# mix_txmix.net
KiCad netlist of a schematic drawn in Altium Designer
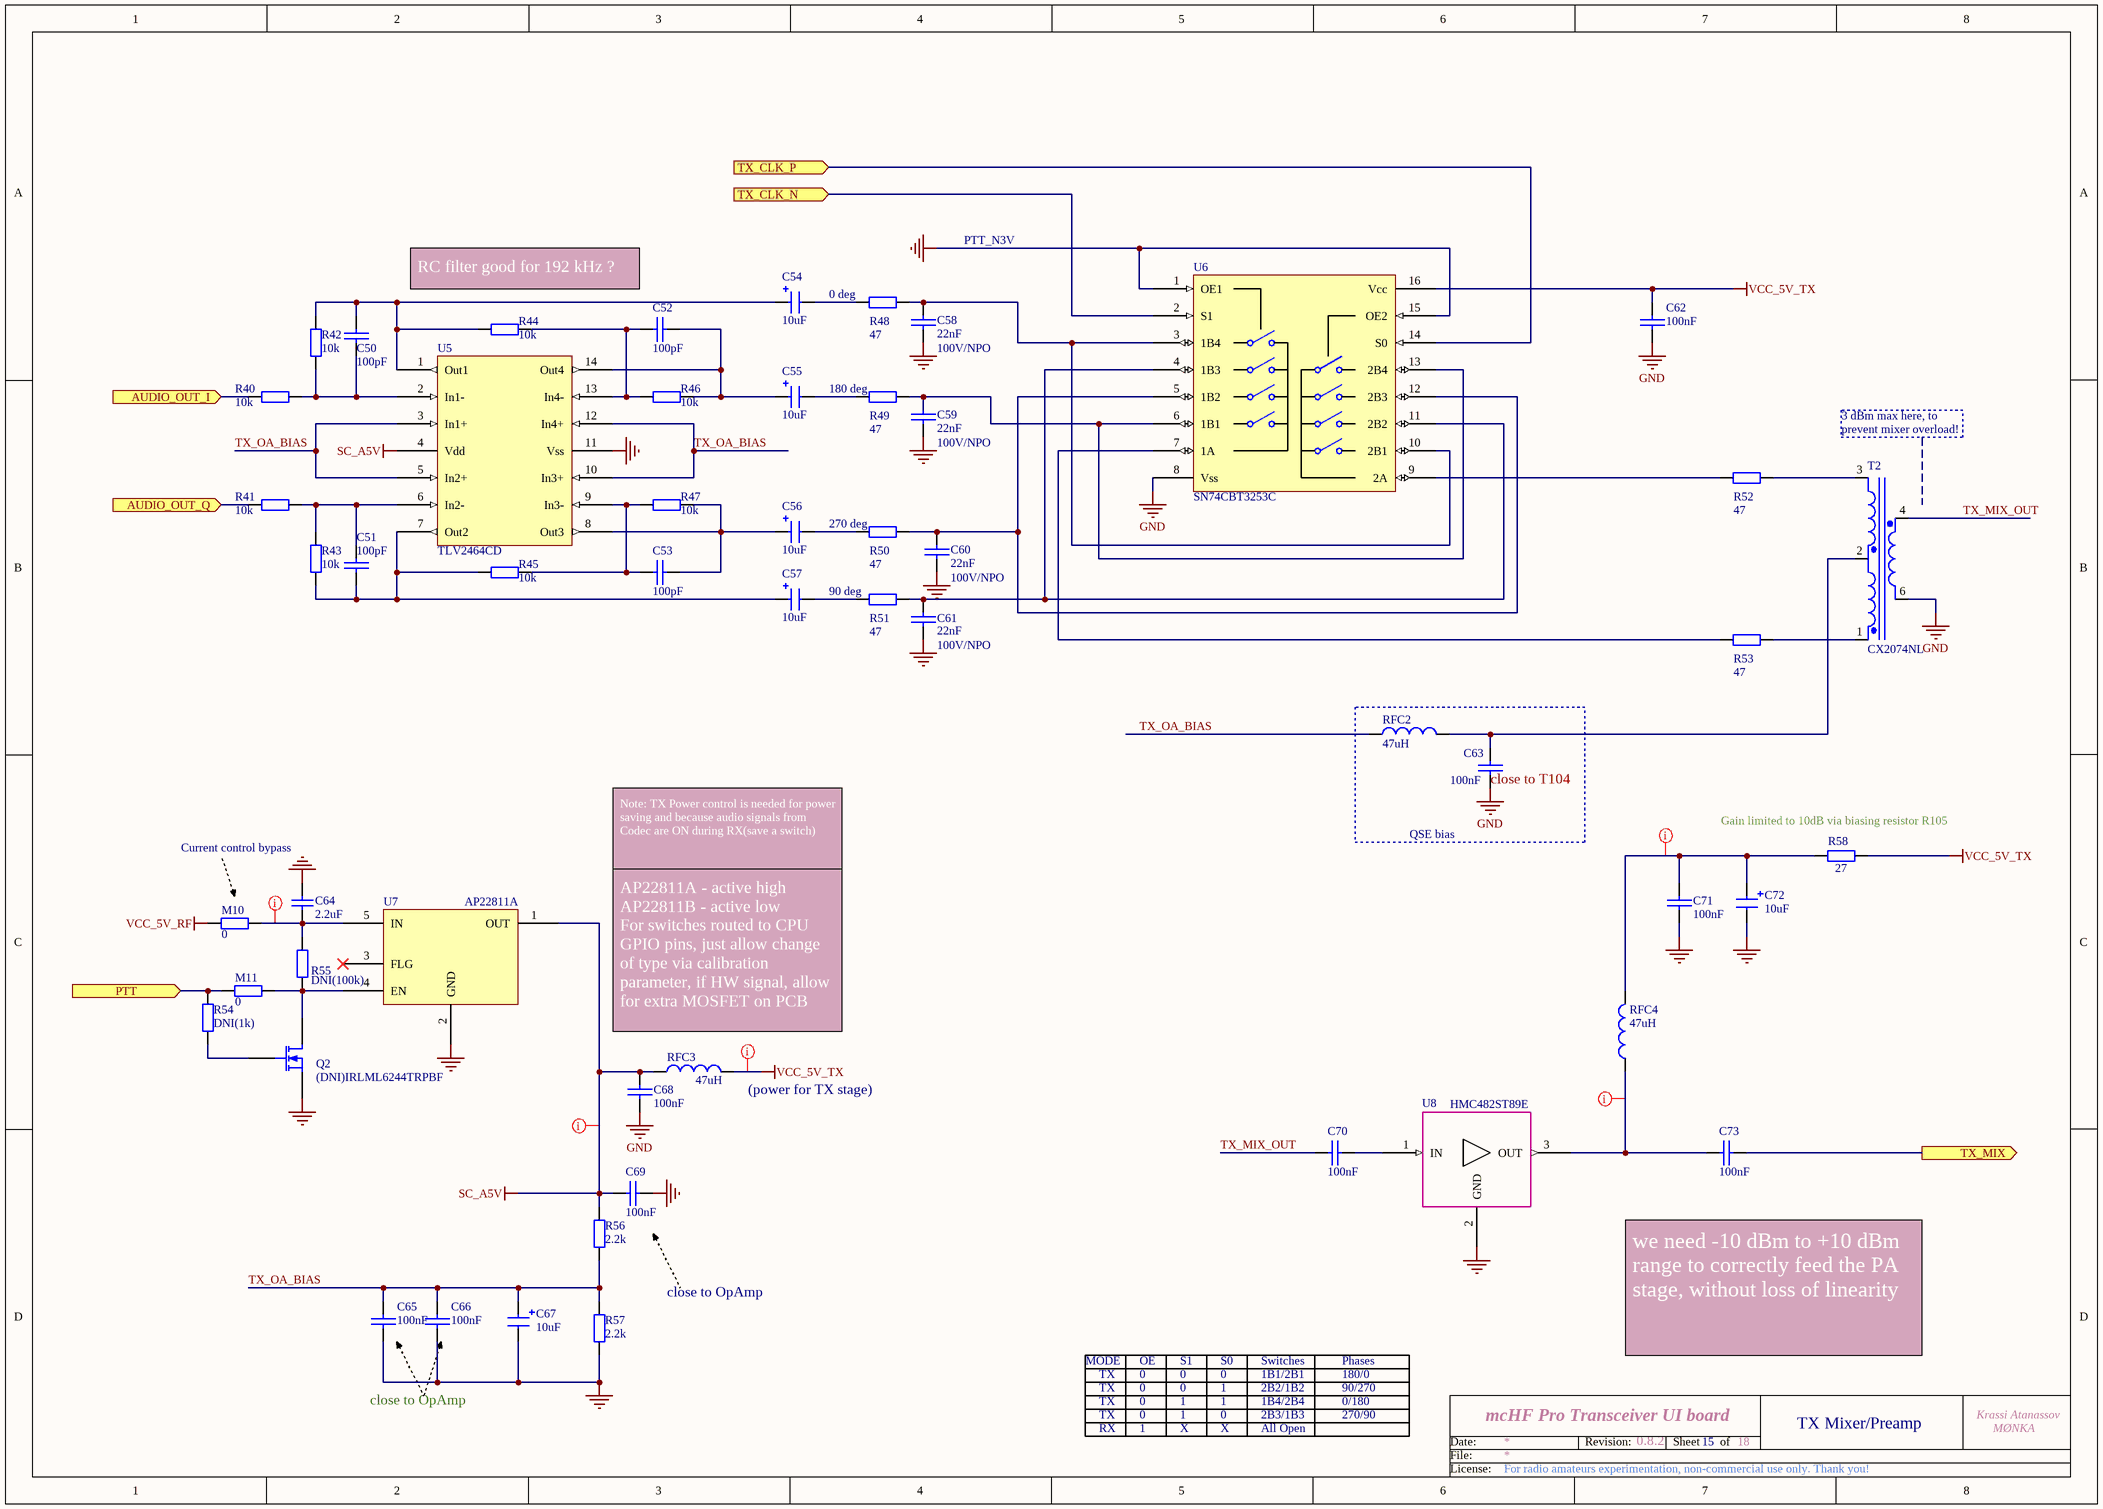
[diagram p0: mix_txmix.SchDoc]

(export (version "E")
  (design (tool "Eeschema 10.0.6"))
  (components
    (comp (ref "C50")
      (value "100pF")
      (footprint "0805")
      (description "Capacitor")
      (libsource (lib "mcHF_rf") (part "CAP"))
    )
    (comp (ref "C51")
      (value "100pF")
      (footprint "0805")
      (description "Capacitor")
      (libsource (lib "mcHF_rf") (part "CAP"))
    )
    (comp (ref "C52")
      (value "100pF")
      (footprint "0805")
      (description "Capacitor")
      (libsource (lib "mcHF_rf") (part "CAP"))
    )
    (comp (ref "C53")
      (value "100pF")
      (footprint "0805")
      (description "Capacitor")
      (libsource (lib "mcHF_rf") (part "CAP"))
    )
    (comp (ref "C54")
      (value "10uF")
      (footprint "1206_Elec_Cap")
      (description "Electrolitic capacitor")
      (libsource (lib "mcHF_rf") (part "CAP-POL"))
    )
    (comp (ref "C55")
      (value "10uF")
      (footprint "1206_Elec_Cap")
      (description "Electrolitic capacitor")
      (libsource (lib "mcHF_rf") (part "CAP-POL"))
    )
    (comp (ref "C56")
      (value "10uF")
      (footprint "1206_Elec_Cap")
      (description "Electrolitic capacitor")
      (libsource (lib "mcHF_rf") (part "CAP-POL"))
    )
    (comp (ref "C57")
      (value "10uF")
      (footprint "1206_Elec_Cap")
      (description "Electrolitic capacitor")
      (libsource (lib "mcHF_rf") (part "CAP-POL"))
    )
    (comp (ref "C58")
      (value "22nF")
      (footprint "CAP_B")
      (description "Capacitor")
      (fields (field (name "VOLTAGE") "100V/NPO"))
      (libsource (lib "mcHF_rf") (part "CAP"))
    )
    (comp (ref "C59")
      (value "22nF")
      (footprint "CAP_B")
      (description "Capacitor")
      (fields (field (name "VOLTAGE") "100V/NPO"))
      (libsource (lib "mcHF_rf") (part "CAP"))
    )
    (comp (ref "C60")
      (value "22nF")
      (footprint "CAP_B")
      (description "Capacitor")
      (fields (field (name "VOLTAGE") "100V/NPO"))
      (libsource (lib "mcHF_rf") (part "CAP"))
    )
    (comp (ref "C61")
      (value "22nF")
      (footprint "CAP_B")
      (description "Capacitor")
      (fields (field (name "VOLTAGE") "100V/NPO"))
      (libsource (lib "mcHF_rf") (part "CAP"))
    )
    (comp (ref "C62")
      (value "100nF")
      (footprint "0805")
      (description "Capacitor")
      (libsource (lib "mcHF_rf") (part "CAP"))
    )
    (comp (ref "C63")
      (value "100nF")
      (footprint "0805")
      (description "Capacitor")
      (libsource (lib "mcHF_rf") (part "CAP"))
    )
    (comp (ref "C64")
      (value "2.2uF")
      (footprint "0805")
      (description "0603  X5R 1礔")
      (fields (field (name "TOLERANCE") "10%"))
      (libsource (lib "MB963_1") (part "CAP SMD 0603  X5R 1礔 25V 10%"))
    )
    (comp (ref "C65")
      (value "100nF")
      (footprint "0805")
      (description "Capacitor")
      (libsource (lib "mcHF_rf") (part "CAP"))
    )
    (comp (ref "C66")
      (value "100nF")
      (footprint "0805")
      (description "Capacitor")
      (libsource (lib "mcHF_rf") (part "CAP"))
    )
    (comp (ref "C67")
      (value "10uF")
      (footprint "1206_Elec_Cap")
      (description "Electrolitic capacitor")
      (libsource (lib "mcHF_rf") (part "CAP-POL"))
    )
    (comp (ref "C68")
      (value "100nF")
      (footprint "0805")
      (description "Capacitor")
      (libsource (lib "mcHF_rf") (part "CAP"))
    )
    (comp (ref "C69")
      (value "100nF")
      (footprint "0805")
      (description "Capacitor")
      (libsource (lib "mcHF_rf") (part "CAP"))
    )
    (comp (ref "C70")
      (value "100nF")
      (footprint "0805")
      (description "Capacitor")
      (libsource (lib "*") (part "CAP"))
    )
    (comp (ref "C71")
      (value "100nF")
      (footprint "0805")
      (description "Capacitor")
      (libsource (lib "*") (part "CAP"))
    )
    (comp (ref "C72")
      (value "10uF")
      (footprint "1206_Elec_Cap")
      (description "Electrolitic capacitor")
      (libsource (lib "mcHF_rf") (part "CAP-POL"))
    )
    (comp (ref "C73")
      (value "100nF")
      (footprint "0805")
      (description "Capacitor")
      (libsource (lib "*") (part "CAP"))
    )
    (comp (ref "M10")
      (value "0")
      (footprint "0805")
      (description "Resistor")
      (libsource (lib "mcHF_rf") (part "RES"))
    )
    (comp (ref "M11")
      (value "0")
      (footprint "0805")
      (description "Resistor")
      (libsource (lib "") (part "RES_1"))
    )
    (comp (ref "Q2")
      (value "(DNI)IRLML6244TRPBF")
      (footprint "SOT-23")
      (description "N-Channel MOSFET")
      (libsource (lib "mcHF_ui_b") (part "MOSFET-N"))
    )
    (comp (ref "R40")
      (value "10k")
      (footprint "0805")
      (description "Resistor")
      (libsource (lib "mcHF_rf") (part "RES"))
    )
    (comp (ref "R41")
      (value "10k")
      (footprint "0805")
      (description "Resistor")
      (libsource (lib "mcHF_rf") (part "RES"))
    )
    (comp (ref "R42")
      (value "10k")
      (footprint "0805")
      (description "Resistor")
      (libsource (lib "") (part "RES_2"))
    )
    (comp (ref "R43")
      (value "10k")
      (footprint "0805")
      (description "Resistor")
      (libsource (lib "") (part "RES_2"))
    )
    (comp (ref "R44")
      (value "10k")
      (footprint "0805")
      (description "Resistor")
      (libsource (lib "mcHF_rf") (part "RES"))
    )
    (comp (ref "R45")
      (value "10k")
      (footprint "0805")
      (description "Resistor")
      (libsource (lib "mcHF_rf") (part "RES"))
    )
    (comp (ref "R46")
      (value "10k")
      (footprint "0805")
      (description "Resistor")
      (libsource (lib "mcHF_rf") (part "RES"))
    )
    (comp (ref "R47")
      (value "10k")
      (footprint "0805")
      (description "Resistor")
      (libsource (lib "mcHF_rf") (part "RES"))
    )
    (comp (ref "R48")
      (value "47")
      (footprint "0805")
      (description "Resistor")
      (libsource (lib "mcHF_rf") (part "RES"))
    )
    (comp (ref "R49")
      (value "47")
      (footprint "0805")
      (description "Resistor")
      (libsource (lib "mcHF_rf") (part "RES"))
    )
    (comp (ref "R50")
      (value "47")
      (footprint "0805")
      (description "Resistor")
      (libsource (lib "mcHF_rf") (part "RES"))
    )
    (comp (ref "R51")
      (value "47")
      (footprint "0805")
      (description "Resistor")
      (libsource (lib "mcHF_rf") (part "RES"))
    )
    (comp (ref "R52")
      (value "47")
      (footprint "0805")
      (description "Resistor")
      (libsource (lib "mcHF_rf") (part "RES"))
    )
    (comp (ref "R53")
      (value "47")
      (footprint "0805")
      (description "Resistor")
      (libsource (lib "mcHF_rf") (part "RES"))
    )
    (comp (ref "R54")
      (value "DNI(1k)")
      (footprint "0805")
      (description "Resistor")
      (libsource (lib "") (part "RES_2"))
    )
    (comp (ref "R55")
      (value "DNI(100k)")
      (footprint "0805")
      (description "Resistor")
      (libsource (lib "mcHF_ui") (part "RES"))
    )
    (comp (ref "R56")
      (value "2.2k")
      (footprint "0805")
      (description "Resistor")
      (libsource (lib "") (part "RES_2"))
    )
    (comp (ref "R57")
      (value "2.2k")
      (footprint "0805")
      (description "Resistor")
      (libsource (lib "") (part "RES_2"))
    )
    (comp (ref "R58")
      (value "27")
      (footprint "1206")
      (description "Resistor")
      (libsource (lib "") (part "RES_1"))
    )
    (comp (ref "RFC2")
      (value "47uH")
      (footprint "0805")
      (description "INDUCTOR, SIGNAL LINE, 4.7UH, 1005")
      (libsource (lib "mcHF_rf") (part "TDK-NLV25T"))
    )
    (comp (ref "RFC3")
      (value "47uH")
      (footprint "0805")
      (description "INDUCTOR, SIGNAL LINE, 4.7UH, 1005")
      (libsource (lib "mcHF_rf") (part "TDK-NLV25T"))
    )
    (comp (ref "RFC4")
      (value "47uH")
      (footprint "0805")
      (description "INDUCTOR, SIGNAL LINE, 4.7UH, 1005")
      (libsource (lib "mcHF_rf") (part "TDK-NLV25T"))
    )
    (comp (ref "T2")
      (value "CX2074NL")
      (footprint "SOP5_NEW1")
      (description "Wideband RF Transformer 1:4")
      (libsource (lib "mcHF_rf") (part "CX2074NL"))
    )
    (comp (ref "U5")
      (value "TLV2464CD")
      (footprint "SO-14-Pro")
      (description "Low Power, Rail-To-Rail OpAmp")
      (libsource (lib "mcHF_rf") (part "TLV2464CD"))
    )
    (comp (ref "U6")
      (value "SN74CBT3253C")
      (footprint "SO-16-Pro")
      (description "Dual 4:1 Demux/Analog Switch")
      (libsource (lib "mcHF_rf") (part "SN74CBT3253C"))
    )
    (comp (ref "U7")
      (value "AP22811A")
      (footprint "SOT25-5")
      (description "High-side switch")
      (libsource (lib "__ui") (part "AP22811"))
    )
    (comp (ref "U8")
      (value "HMC482ST89E")
      (footprint "SOT89L_new")
      (description "MMIC AMPLIFIER")
      (libsource (lib "mcHF_rf") (part "HMS482ST89E"))
    )
  )
  (nets
    (net (code "1") (name "/AUDIO_OUT_I") (class "Default")
      (node (ref "R40") (pin "1") (pinfunction "1_1") (pintype "passive"))
    )
    (net (code "2") (name "/AUDIO_OUT_Q") (class "Default")
      (node (ref "R41") (pin "1") (pinfunction "1_1") (pintype "passive"))
    )
    (net (code "3") (name "/PTT") (class "Default")
      (node (ref "M11") (pin "2") (pinfunction "2_2") (pintype "passive"))
      (node (ref "R54") (pin "2") (pinfunction "2_2") (pintype "passive"))
    )
    (net (code "4") (name "/TX_CLK_N") (class "Default")
      (node (ref "U6") (pin "2") (pinfunction "S1_2") (pintype "input"))
    )
    (net (code "5") (name "/TX_CLK_P") (class "Default")
      (node (ref "U6") (pin "14") (pinfunction "S0_14") (pintype "input"))
    )
    (net (code "6") (name "/TX_MIX") (class "Default")
      (node (ref "C73") (pin "1") (pinfunction "1_1") (pintype "passive"))
    )
    (net (code "7") (name "/TX_MIX_OUT") (class "Default")
      (node (ref "C70") (pin "2") (pinfunction "2_2") (pintype "passive"))
      (node (ref "T2") (pin "4") (pinfunction "Pri-_4") (pintype "passive"))
    )
    (net (code "8") (name "/TX_OA_BIAS") (class "Default")
      (node (ref "C65") (pin "2") (pinfunction "2_2") (pintype "passive"))
      (node (ref "C66") (pin "2") (pinfunction "2_2") (pintype "passive"))
      (node (ref "C67") (pin "1") (pinfunction "1_1") (pintype "passive"))
      (node (ref "R56") (pin "1") (pinfunction "1_1") (pintype "passive"))
      (node (ref "R57") (pin "2") (pinfunction "2_2") (pintype "passive"))
      (node (ref "RFC2") (pin "1") (pinfunction "1_1") (pintype "passive"))
      (node (ref "U5") (pin "10") (pinfunction "In3+_10") (pintype "input"))
      (node (ref "U5") (pin "12") (pinfunction "In4+_12") (pintype "input"))
      (node (ref "U5") (pin "3") (pinfunction "In1+_3") (pintype "input"))
      (node (ref "U5") (pin "5") (pinfunction "In2+_5") (pintype "input"))
    )
    (net (code "9") (name "GND") (class "Default")
      (node (ref "C58") (pin "2") (pinfunction "2_2") (pintype "passive"))
      (node (ref "C59") (pin "2") (pinfunction "2_2") (pintype "passive"))
      (node (ref "C60") (pin "2") (pinfunction "2_2") (pintype "passive"))
      (node (ref "C61") (pin "2") (pinfunction "2_2") (pintype "passive"))
      (node (ref "C62") (pin "1") (pinfunction "1_1") (pintype "passive"))
      (node (ref "C63") (pin "1") (pinfunction "1_1") (pintype "passive"))
      (node (ref "C64") (pin "1") (pinfunction "1_1") (pintype "passive"))
      (node (ref "C65") (pin "1") (pinfunction "1_1") (pintype "passive"))
      (node (ref "C66") (pin "1") (pinfunction "1_1") (pintype "passive"))
      (node (ref "C67") (pin "2") (pinfunction "2_2") (pintype "passive"))
      (node (ref "C68") (pin "1") (pinfunction "1_1") (pintype "passive"))
      (node (ref "C69") (pin "1") (pinfunction "1_1") (pintype "passive"))
      (node (ref "C71") (pin "2") (pinfunction "2_2") (pintype "passive"))
      (node (ref "C72") (pin "2") (pinfunction "2_2") (pintype "passive"))
      (node (ref "Q2") (pin "2") (pinfunction "S_2") (pintype "passive"))
      (node (ref "R57") (pin "1") (pinfunction "1_1") (pintype "passive"))
      (node (ref "T2") (pin "6") (pinfunction "Pri+_6") (pintype "passive"))
      (node (ref "U5") (pin "11") (pinfunction "Vss_11") (pintype "power_in"))
      (node (ref "U6") (pin "1") (pinfunction "OE1_1") (pintype "input"))
      (node (ref "U6") (pin "15") (pinfunction "OE2_15") (pintype "input"))
      (node (ref "U6") (pin "8") (pinfunction "Vss_8") (pintype "power_in"))
      (node (ref "U7") (pin "2") (pinfunction "GND_2") (pintype "passive"))
      (node (ref "U8") (pin "2") (pinfunction "GND_2") (pintype "power_in"))
    )
    (net (code "10") (name "Net-(C54-Pad2)") (class "Default")
      (node (ref "C54") (pin "2") (pinfunction "2_2") (pintype "passive"))
      (node (ref "R48") (pin "1") (pinfunction "1_1") (pintype "passive"))
    )
    (net (code "11") (name "Net-(C55-Pad2)") (class "Default")
      (node (ref "C55") (pin "2") (pinfunction "2_2") (pintype "passive"))
      (node (ref "R49") (pin "1") (pinfunction "1_1") (pintype "passive"))
    )
    (net (code "12") (name "Net-(C56-Pad2)") (class "Default")
      (node (ref "C56") (pin "2") (pinfunction "2_2") (pintype "passive"))
      (node (ref "R50") (pin "1") (pinfunction "1_1") (pintype "passive"))
    )
    (net (code "13") (name "Net-(C57-Pad2)") (class "Default")
      (node (ref "C57") (pin "2") (pinfunction "2_2") (pintype "passive"))
      (node (ref "R51") (pin "1") (pinfunction "1_1") (pintype "passive"))
    )
    (net (code "14") (name "Net-(C71-Pad1)") (class "Default")
      (node (ref "C71") (pin "1") (pinfunction "1_1") (pintype "passive"))
      (node (ref "C72") (pin "1") (pinfunction "1_1") (pintype "passive"))
      (node (ref "R58") (pin "2") (pinfunction "2_2") (pintype "passive"))
      (node (ref "RFC4") (pin "2") (pinfunction "2_2") (pintype "passive"))
    )
    (net (code "15") (name "Net-(Q2-D)") (class "Default")
      (node (ref "M11") (pin "1") (pinfunction "1_1") (pintype "passive"))
      (node (ref "Q2") (pin "3") (pinfunction "D_3") (pintype "passive"))
      (node (ref "R55") (pin "2") (pinfunction "2_2") (pintype "passive"))
      (node (ref "U7") (pin "4") (pinfunction "EN_4") (pintype "passive"))
    )
    (net (code "16") (name "Net-(Q2-G)") (class "Default")
      (node (ref "Q2") (pin "1") (pinfunction "G_1") (pintype "passive"))
      (node (ref "R54") (pin "1") (pinfunction "1_1") (pintype "passive"))
    )
    (net (code "17") (name "Net-(T2-Sec0)") (class "Default")
      (node (ref "R53") (pin "2") (pinfunction "2_2") (pintype "passive"))
      (node (ref "T2") (pin "1") (pinfunction "Sec0_1") (pintype "passive"))
    )
    (net (code "18") (name "Net-(T2-Sec180)") (class "Default")
      (node (ref "R52") (pin "2") (pinfunction "2_2") (pintype "passive"))
      (node (ref "T2") (pin "3") (pinfunction "Sec180_3") (pintype "passive"))
    )
    (net (code "19") (name "Net-(T2-SecCmn)") (class "Default")
      (node (ref "C63") (pin "2") (pinfunction "2_2") (pintype "passive"))
      (node (ref "RFC2") (pin "2") (pinfunction "2_2") (pintype "passive"))
      (node (ref "T2") (pin "2") (pinfunction "SecCmn_2") (pintype "passive"))
    )
    (net (code "20") (name "Net-(U5-In1-)") (class "Default")
      (node (ref "C50") (pin "1") (pinfunction "1_1") (pintype "passive"))
      (node (ref "R40") (pin "2") (pinfunction "2_2") (pintype "passive"))
      (node (ref "R42") (pin "1") (pinfunction "1_1") (pintype "passive"))
      (node (ref "U5") (pin "2") (pinfunction "In1-_2") (pintype "input"))
    )
    (net (code "21") (name "Net-(U5-In2-)") (class "Default")
      (node (ref "C51") (pin "2") (pinfunction "2_2") (pintype "passive"))
      (node (ref "R41") (pin "2") (pinfunction "2_2") (pintype "passive"))
      (node (ref "R43") (pin "2") (pinfunction "2_2") (pintype "passive"))
      (node (ref "U5") (pin "6") (pinfunction "In2-_6") (pintype "input"))
    )
    (net (code "22") (name "Net-(U5-In3-)") (class "Default")
      (node (ref "C53") (pin "2") (pinfunction "2_2") (pintype "passive"))
      (node (ref "R45") (pin "2") (pinfunction "2_2") (pintype "passive"))
      (node (ref "R47") (pin "1") (pinfunction "1_1") (pintype "passive"))
      (node (ref "U5") (pin "9") (pinfunction "In3-_9") (pintype "input"))
    )
    (net (code "23") (name "Net-(U5-In4-)") (class "Default")
      (node (ref "C52") (pin "2") (pinfunction "2_2") (pintype "passive"))
      (node (ref "R44") (pin "2") (pinfunction "2_2") (pintype "passive"))
      (node (ref "R46") (pin "1") (pinfunction "1_1") (pintype "passive"))
      (node (ref "U5") (pin "13") (pinfunction "In4-_13") (pintype "input"))
    )
    (net (code "24") (name "Net-(U5-Out1)") (class "Default")
      (node (ref "C50") (pin "2") (pinfunction "2_2") (pintype "passive"))
      (node (ref "C54") (pin "1") (pinfunction "1_1") (pintype "passive"))
      (node (ref "R42") (pin "2") (pinfunction "2_2") (pintype "passive"))
      (node (ref "R44") (pin "1") (pinfunction "1_1") (pintype "passive"))
      (node (ref "U5") (pin "1") (pinfunction "Out1_1") (pintype "output"))
    )
    (net (code "25") (name "Net-(U5-Out2)") (class "Default")
      (node (ref "C51") (pin "1") (pinfunction "1_1") (pintype "passive"))
      (node (ref "C57") (pin "1") (pinfunction "1_1") (pintype "passive"))
      (node (ref "R43") (pin "1") (pinfunction "1_1") (pintype "passive"))
      (node (ref "R45") (pin "1") (pinfunction "1_1") (pintype "passive"))
      (node (ref "U5") (pin "7") (pinfunction "Out2_7") (pintype "output"))
    )
    (net (code "26") (name "Net-(U5-Out3)") (class "Default")
      (node (ref "C53") (pin "1") (pinfunction "1_1") (pintype "passive"))
      (node (ref "C56") (pin "1") (pinfunction "1_1") (pintype "passive"))
      (node (ref "R47") (pin "2") (pinfunction "2_2") (pintype "passive"))
      (node (ref "U5") (pin "8") (pinfunction "Out3_8") (pintype "output"))
    )
    (net (code "27") (name "Net-(U5-Out4)") (class "Default")
      (node (ref "C52") (pin "1") (pinfunction "1_1") (pintype "passive"))
      (node (ref "C55") (pin "1") (pinfunction "1_1") (pintype "passive"))
      (node (ref "R46") (pin "2") (pinfunction "2_2") (pintype "passive"))
      (node (ref "U5") (pin "14") (pinfunction "Out4_14") (pintype "output"))
    )
    (net (code "28") (name "Net-(U6-1A)") (class "Default")
      (node (ref "R53") (pin "1") (pinfunction "1_1") (pintype "passive"))
      (node (ref "U6") (pin "7") (pinfunction "1A_7") (pintype "bidirectional"))
    )
    (net (code "29") (name "Net-(U6-1B1)") (class "Default")
      (node (ref "C59") (pin "1") (pinfunction "1_1") (pintype "passive"))
      (node (ref "R49") (pin "2") (pinfunction "2_2") (pintype "passive"))
      (node (ref "U6") (pin "13") (pinfunction "2B4_13") (pintype "bidirectional"))
      (node (ref "U6") (pin "6") (pinfunction "1B1_6") (pintype "bidirectional"))
    )
    (net (code "30") (name "Net-(U6-1B2)") (class "Default")
      (node (ref "C60") (pin "1") (pinfunction "1_1") (pintype "passive"))
      (node (ref "R50") (pin "2") (pinfunction "2_2") (pintype "passive"))
      (node (ref "U6") (pin "12") (pinfunction "2B3_12") (pintype "bidirectional"))
      (node (ref "U6") (pin "5") (pinfunction "1B2_5") (pintype "bidirectional"))
    )
    (net (code "31") (name "Net-(U6-1B3)") (class "Default")
      (node (ref "C61") (pin "1") (pinfunction "1_1") (pintype "passive"))
      (node (ref "R51") (pin "2") (pinfunction "2_2") (pintype "passive"))
      (node (ref "U6") (pin "11") (pinfunction "2B2_11") (pintype "bidirectional"))
      (node (ref "U6") (pin "4") (pinfunction "1B3_4") (pintype "bidirectional"))
    )
    (net (code "32") (name "Net-(U6-1B4)") (class "Default")
      (node (ref "C58") (pin "1") (pinfunction "1_1") (pintype "passive"))
      (node (ref "R48") (pin "2") (pinfunction "2_2") (pintype "passive"))
      (node (ref "U6") (pin "10") (pinfunction "2B1_10") (pintype "bidirectional"))
      (node (ref "U6") (pin "3") (pinfunction "1B4_3") (pintype "bidirectional"))
    )
    (net (code "33") (name "Net-(U6-2A)") (class "Default")
      (node (ref "R52") (pin "1") (pinfunction "1_1") (pintype "passive"))
      (node (ref "U6") (pin "9") (pinfunction "2A_9") (pintype "bidirectional"))
    )
    (net (code "34") (name "Net-(U7-IN)") (class "Default")
      (node (ref "C64") (pin "2") (pinfunction "2_2") (pintype "passive"))
      (node (ref "M10") (pin "2") (pinfunction "2_2") (pintype "passive"))
      (node (ref "R55") (pin "1") (pinfunction "1_1") (pintype "passive"))
      (node (ref "U7") (pin "5") (pinfunction "IN_5") (pintype "power_in"))
    )
    (net (code "35") (name "Net-(U8-IN)") (class "Default")
      (node (ref "C70") (pin "1") (pinfunction "1_1") (pintype "passive"))
      (node (ref "U8") (pin "1") (pinfunction "IN_1") (pintype "input"))
    )
    (net (code "36") (name "Net-(U8-OUT)") (class "Default")
      (node (ref "C73") (pin "2") (pinfunction "2_2") (pintype "passive"))
      (node (ref "RFC4") (pin "1") (pinfunction "1_1") (pintype "passive"))
      (node (ref "U8") (pin "3") (pinfunction "OUT_3") (pintype "output"))
    )
    (net (code "37") (name "SC_A5V") (class "Default")
      (node (ref "C68") (pin "2") (pinfunction "2_2") (pintype "passive"))
      (node (ref "C69") (pin "2") (pinfunction "2_2") (pintype "passive"))
      (node (ref "R56") (pin "2") (pinfunction "2_2") (pintype "passive"))
      (node (ref "RFC3") (pin "1") (pinfunction "1_1") (pintype "passive"))
      (node (ref "U5") (pin "4") (pinfunction "Vdd_4") (pintype "power_in"))
      (node (ref "U7") (pin "1") (pinfunction "OUT_1") (pintype "power_in"))
    )
    (net (code "38") (name "VCC_5V_RF") (class "Default")
      (node (ref "M10") (pin "1") (pinfunction "1_1") (pintype "passive"))
    )
    (net (code "39") (name "VCC_5V_TX") (class "Default")
      (node (ref "C62") (pin "2") (pinfunction "2_2") (pintype "passive"))
      (node (ref "R58") (pin "1") (pinfunction "1_1") (pintype "passive"))
      (node (ref "RFC3") (pin "2") (pinfunction "2_2") (pintype "passive"))
      (node (ref "U6") (pin "16") (pinfunction "Vcc_16") (pintype "power_in"))
    )
    (net (code "40") (name "unconnected-(U7-FLG-Pad3)") (class "Default")
      (node (ref "U7") (pin "3") (pinfunction "FLG_3") (pintype "passive+no_connect"))
    )
  )
)
